# V3.net
KiCad netlist of a schematic drawn in Altium Designer
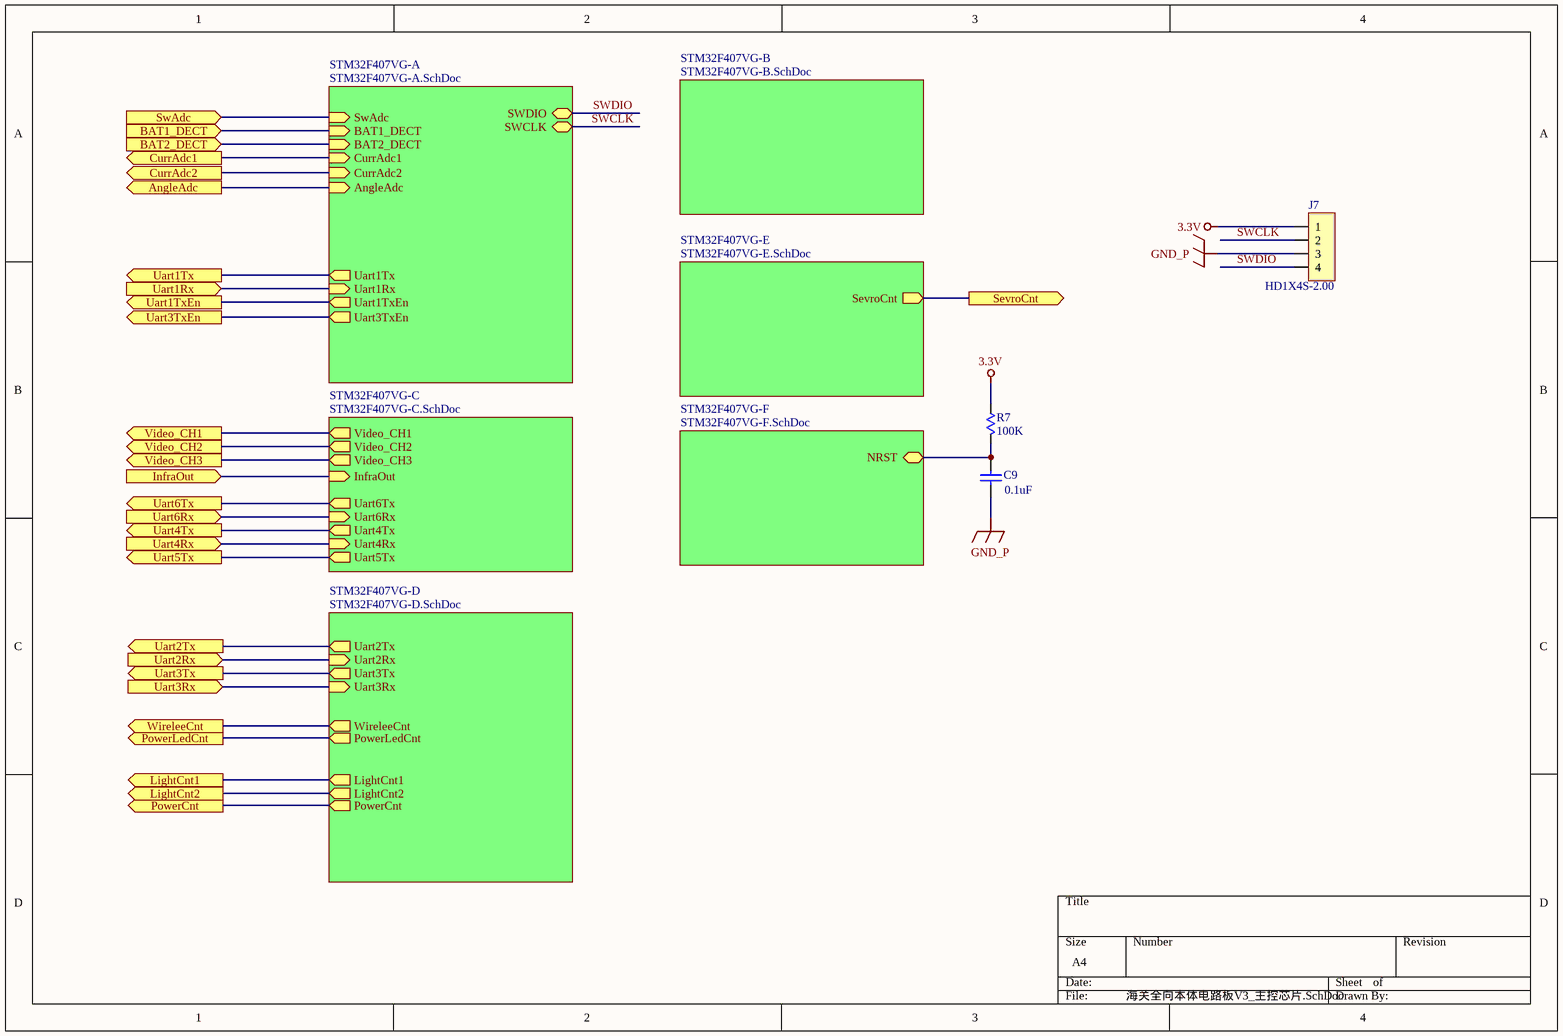
[diagram p0: 海关全向本体电路板V3_主控芯片.SchDoc]

(export (version "E")
  (design (tool "Eeschema 10.0.6"))
  (components
    (comp (ref "C9")
      (value "0.1uF")
      (footprint "C0603-S")
      (description "Capacitor")
      (fields (field (name "PUBLISHER") "Altium Limited"))
      (libsource (lib "Miscellaneous Devices") (part "Cap"))
    )
    (comp (ref "J7")
      (value "HD1X4S-2.00")
      (footprint "HD1X4S-2.00")
      (libsource (lib "Connector Class") (part "HEADER1X4"))
    )
    (comp (ref "R7")
      (value "100K")
      (footprint "R0603-S")
      (description "Resistor")
      (fields (field (name "PUBLISHER") "Altium Limited"))
      (libsource (lib "Temp") (part "Res"))
    )
  )
  (nets
    (net (code "9") (name "/NRST") (class "Default")
      (node (ref "C9") (pin "1") (pinfunction "1_1") (pintype "passive"))
      (node (ref "R7") (pin "1") (pinfunction "1_1") (pintype "passive"))
    )
    (net (code "12") (name "/SWCLK") (class "Default")
      (node (ref "J7") (pin "2") (pinfunction "2_2") (pintype "passive"))
    )
    (net (code "13") (name "/SWDIO") (class "Default")
      (node (ref "J7") (pin "4") (pinfunction "4_4") (pintype "passive"))
    )
    (net (code "33") (name "3.3V") (class "Default")
      (node (ref "J7") (pin "1") (pinfunction "1_1") (pintype "passive"))
      (node (ref "R7") (pin "2") (pinfunction "2_2") (pintype "passive"))
    )
    (net (code "34") (name "GND_P") (class "Default")
      (node (ref "C9") (pin "2") (pinfunction "2_2") (pintype "passive"))
      (node (ref "J7") (pin "3") (pinfunction "3_3") (pintype "passive"))
    )
  )
)
